# d102-spinsemi-fx.net
KiCad netlist of a schematic drawn in EAGLE
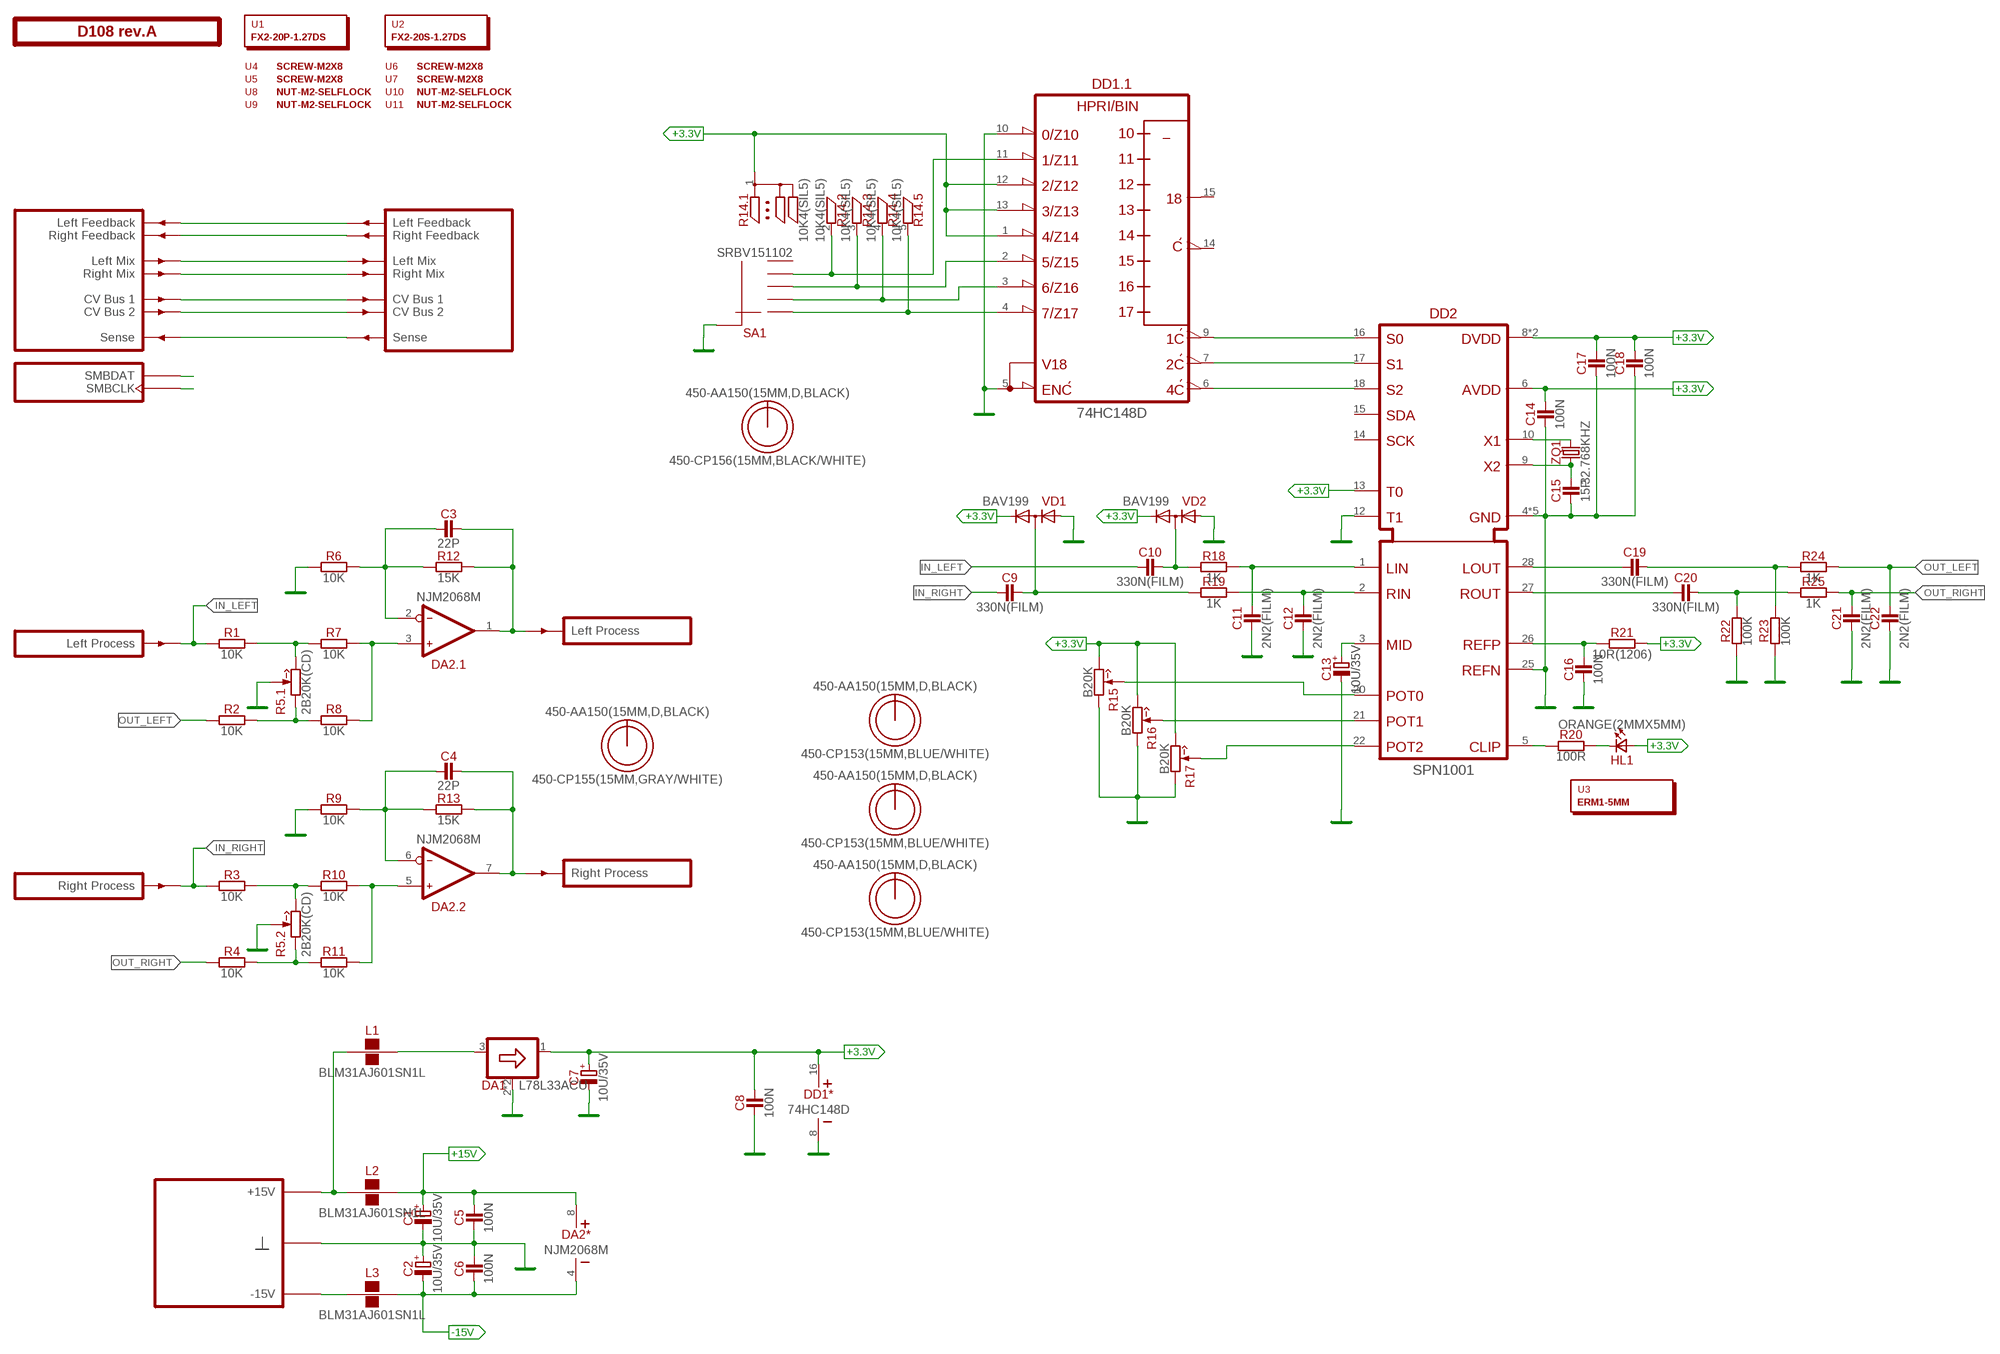
[diagram p0: schematic, sheet 1]

(export (version "E")
  (design (tool "Eeschema 10.0.6"))
  (components
    (comp (ref "C1")
      (value "10U/35V")
      (footprint "eagle-import:E2-5")
      (libsource (lib "eagle-import") (part "?10U/35V"))
    )
    (comp (ref "C2")
      (value "10U/35V")
      (footprint "eagle-import:E2-5")
      (libsource (lib "eagle-import") (part "?10U/35V"))
    )
    (comp (ref "C3")
      (value "22P")
      (footprint "eagle-import:C-0805")
      (libsource (lib "eagle-import") (part "?22P"))
    )
    (comp (ref "C4")
      (value "22P")
      (footprint "eagle-import:C-0805")
      (libsource (lib "eagle-import") (part "?22P"))
    )
    (comp (ref "C5")
      (value "100N")
      (footprint "eagle-import:C-0805")
      (libsource (lib "eagle-import") (part "?100N"))
    )
    (comp (ref "C6")
      (value "100N")
      (footprint "eagle-import:C-0805")
      (libsource (lib "eagle-import") (part "?100N"))
    )
    (comp (ref "C7")
      (value "10U/35V")
      (footprint "eagle-import:E2-5")
      (libsource (lib "eagle-import") (part "?10U/35V"))
    )
    (comp (ref "C8")
      (value "100N")
      (footprint "eagle-import:C-0805")
      (libsource (lib "eagle-import") (part "?100N"))
    )
    (comp (ref "C9")
      (value "330N(FILM)")
      (footprint "eagle-import:C050-035X075")
      (libsource (lib "eagle-import") (part "?330N(FILM)"))
    )
    (comp (ref "C10")
      (value "330N(FILM)")
      (footprint "eagle-import:C050-035X075")
      (libsource (lib "eagle-import") (part "?330N(FILM)"))
    )
    (comp (ref "C11")
      (value "2N2(FILM)")
      (footprint "eagle-import:C050-025X075")
      (libsource (lib "eagle-import") (part "?2N2(FILM)"))
    )
    (comp (ref "C12")
      (value "2N2(FILM)")
      (footprint "eagle-import:C050-025X075")
      (libsource (lib "eagle-import") (part "?2N2(FILM)"))
    )
    (comp (ref "C13")
      (value "10U/35V")
      (footprint "eagle-import:E2-5")
      (libsource (lib "eagle-import") (part "?10U/35V"))
    )
    (comp (ref "C14")
      (value "100N")
      (footprint "eagle-import:C-0805")
      (libsource (lib "eagle-import") (part "?100N"))
    )
    (comp (ref "C15")
      (value "15P")
      (footprint "eagle-import:C-0805")
      (libsource (lib "eagle-import") (part "?15P"))
    )
    (comp (ref "C16")
      (value "100N")
      (footprint "eagle-import:C-0805")
      (libsource (lib "eagle-import") (part "?100N"))
    )
    (comp (ref "C17")
      (value "100N")
      (footprint "eagle-import:C-0805")
      (libsource (lib "eagle-import") (part "?100N"))
    )
    (comp (ref "C18")
      (value "100N")
      (footprint "eagle-import:C-0805")
      (libsource (lib "eagle-import") (part "?100N"))
    )
    (comp (ref "C19")
      (value "330N(FILM)")
      (footprint "eagle-import:C050-035X075")
      (libsource (lib "eagle-import") (part "?330N(FILM)"))
    )
    (comp (ref "C20")
      (value "330N(FILM)")
      (footprint "eagle-import:C050-035X075")
      (libsource (lib "eagle-import") (part "?330N(FILM)"))
    )
    (comp (ref "C21")
      (value "2N2(FILM)")
      (footprint "eagle-import:C050-025X075")
      (libsource (lib "eagle-import") (part "?2N2(FILM)"))
    )
    (comp (ref "C22")
      (value "2N2(FILM)")
      (footprint "eagle-import:C050-025X075")
      (libsource (lib "eagle-import") (part "?2N2(FILM)"))
    )
    (comp (ref "DA1")
      (value "L78L33ACU")
      (footprint "eagle-import:SOT89")
      (libsource (lib "eagle-import") (part "?L78L33ACU"))
    )
    (comp (ref "DA2")
      (value "NJM2068M")
      (footprint "eagle-import:SO-8")
      (libsource (lib "eagle-import") (part "NJM2068M"))
    )
    (comp (ref "DD1")
      (value "74HC148D")
      (footprint "eagle-import:SO-16")
      (libsource (lib "eagle-import") (part "74148?DHC"))
    )
    (comp (ref "DD2")
      (value "SPN1001")
      (footprint "eagle-import:SO28W")
      (libsource (lib "eagle-import") (part "SPN1001"))
    )
    (comp (ref "HL1")
      (value "ORANGE(2MMX5MM)")
      (footprint "eagle-import:LED2X5")
      (libsource (lib "eagle-import") (part "?(2MMX5MM)ORANGE"))
    )
    (comp (ref "L1")
      (value "BLM31AJ601SN1L")
      (footprint "eagle-import:1206")
      (libsource (lib "eagle-import") (part "BLM31AJ601SN1L"))
    )
    (comp (ref "L2")
      (value "BLM31AJ601SN1L")
      (footprint "eagle-import:1206")
      (libsource (lib "eagle-import") (part "BLM31AJ601SN1L"))
    )
    (comp (ref "L3")
      (value "BLM31AJ601SN1L")
      (footprint "eagle-import:1206")
      (libsource (lib "eagle-import") (part "BLM31AJ601SN1L"))
    )
    (comp (ref "O2")
      (value "450-AA150(15MM,D,BLACK)")
      (footprint "eagle-import:EMPTY")
      (libsource (lib "eagle-import") (part "450-AA?150(15MM,D,BLACK)"))
    )
    (comp (ref "O3")
      (value "450-CP155(15MM,GRAY/WHITE)")
      (footprint "eagle-import:EMPTY")
      (libsource (lib "eagle-import") (part "450-C?P155(15MM,GRAY/WHITE)"))
    )
    (comp (ref "O4")
      (value "450-AA150(15MM,D,BLACK)")
      (footprint "eagle-import:EMPTY")
      (libsource (lib "eagle-import") (part "450-AA?150(15MM,D,BLACK)"))
    )
    (comp (ref "O5")
      (value "450-CP156(15MM,BLACK/WHITE)")
      (footprint "eagle-import:EMPTY")
      (libsource (lib "eagle-import") (part "450-C?P156(15MM,BLACK/WHITE)"))
    )
    (comp (ref "O6")
      (value "450-AA150(15MM,D,BLACK)")
      (footprint "eagle-import:EMPTY")
      (libsource (lib "eagle-import") (part "450-AA?150(15MM,D,BLACK)"))
    )
    (comp (ref "O7")
      (value "450-CP153(15MM,BLUE/WHITE)")
      (footprint "eagle-import:EMPTY")
      (libsource (lib "eagle-import") (part "450-C?P153(15MM,BLUE/WHITE)"))
    )
    (comp (ref "O8")
      (value "450-AA150(15MM,D,BLACK)")
      (footprint "eagle-import:EMPTY")
      (libsource (lib "eagle-import") (part "450-AA?150(15MM,D,BLACK)"))
    )
    (comp (ref "O9")
      (value "450-CP153(15MM,BLUE/WHITE)")
      (footprint "eagle-import:EMPTY")
      (libsource (lib "eagle-import") (part "450-C?P153(15MM,BLUE/WHITE)"))
    )
    (comp (ref "O10")
      (value "450-AA150(15MM,D,BLACK)")
      (footprint "eagle-import:EMPTY")
      (libsource (lib "eagle-import") (part "450-AA?150(15MM,D,BLACK)"))
    )
    (comp (ref "O11")
      (value "450-CP153(15MM,BLUE/WHITE)")
      (footprint "eagle-import:EMPTY")
      (libsource (lib "eagle-import") (part "450-C?P153(15MM,BLUE/WHITE)"))
    )
    (comp (ref "PCB1")
      (value "D108 rev.A")
      (footprint "eagle-import:ST2-BOARD-50")
      (libsource (lib "eagle-import") (part "ST2-BOARD-?50"))
    )
    (comp (ref "R1")
      (value "10K")
      (footprint "eagle-import:R-0805")
      (libsource (lib "eagle-import") (part "?10K"))
    )
    (comp (ref "R2")
      (value "10K")
      (footprint "eagle-import:R-0805")
      (libsource (lib "eagle-import") (part "?10K"))
    )
    (comp (ref "R3")
      (value "10K")
      (footprint "eagle-import:R-0805")
      (libsource (lib "eagle-import") (part "?10K"))
    )
    (comp (ref "R4")
      (value "10K")
      (footprint "eagle-import:R-0805")
      (libsource (lib "eagle-import") (part "?10K"))
    )
    (comp (ref "R5")
      (value "2B20K(CD)")
      (footprint "eagle-import:RV11-DUAL")
      (libsource (lib "eagle-import") (part "2?B20K(CD)"))
    )
    (comp (ref "R6")
      (value "10K")
      (footprint "eagle-import:R-0805")
      (libsource (lib "eagle-import") (part "?10K"))
    )
    (comp (ref "R7")
      (value "10K")
      (footprint "eagle-import:R-0805")
      (libsource (lib "eagle-import") (part "?10K"))
    )
    (comp (ref "R8")
      (value "10K")
      (footprint "eagle-import:R-0805")
      (libsource (lib "eagle-import") (part "?10K"))
    )
    (comp (ref "R9")
      (value "10K")
      (footprint "eagle-import:R-0805")
      (libsource (lib "eagle-import") (part "?10K"))
    )
    (comp (ref "R10")
      (value "10K")
      (footprint "eagle-import:R-0805")
      (libsource (lib "eagle-import") (part "?10K"))
    )
    (comp (ref "R11")
      (value "10K")
      (footprint "eagle-import:R-0805")
      (libsource (lib "eagle-import") (part "?10K"))
    )
    (comp (ref "R12")
      (value "15K")
      (footprint "eagle-import:R-0805")
      (libsource (lib "eagle-import") (part "?15K"))
    )
    (comp (ref "R13")
      (value "15K")
      (footprint "eagle-import:R-0805")
      (libsource (lib "eagle-import") (part "?15K"))
    )
    (comp (ref "R14")
      (value "10K4(SIL5)")
      (footprint "eagle-import:R-SIL5")
      (libsource (lib "eagle-import") (part "?4(SIL5)10K"))
    )
    (comp (ref "R15")
      (value "B20K")
      (footprint "eagle-import:RV11-SINGLE")
      (libsource (lib "eagle-import") (part "?B20K"))
    )
    (comp (ref "R16")
      (value "B20K")
      (footprint "eagle-import:RV11-SINGLE")
      (libsource (lib "eagle-import") (part "?B20K"))
    )
    (comp (ref "R17")
      (value "B20K")
      (footprint "eagle-import:RV11-SINGLE")
      (libsource (lib "eagle-import") (part "?B20K"))
    )
    (comp (ref "R18")
      (value "1K")
      (footprint "eagle-import:R-0805")
      (libsource (lib "eagle-import") (part "?1K"))
    )
    (comp (ref "R19")
      (value "1K")
      (footprint "eagle-import:R-0805")
      (libsource (lib "eagle-import") (part "?1K"))
    )
    (comp (ref "R20")
      (value "100R")
      (footprint "eagle-import:R-0805")
      (libsource (lib "eagle-import") (part "?100R"))
    )
    (comp (ref "R21")
      (value "10R(1206)")
      (footprint "eagle-import:R-1206")
      (libsource (lib "eagle-import") (part "?10R(1206)"))
    )
    (comp (ref "R22")
      (value "100K")
      (footprint "eagle-import:R-0805")
      (libsource (lib "eagle-import") (part "?100K"))
    )
    (comp (ref "R23")
      (value "100K")
      (footprint "eagle-import:R-0805")
      (libsource (lib "eagle-import") (part "?100K"))
    )
    (comp (ref "R24")
      (value "1K")
      (footprint "eagle-import:R-0805")
      (libsource (lib "eagle-import") (part "?1K"))
    )
    (comp (ref "R25")
      (value "1K")
      (footprint "eagle-import:R-0805")
      (libsource (lib "eagle-import") (part "?1K"))
    )
    (comp (ref "SA1")
      (value "SRBV151102")
      (footprint "eagle-import:SRBV")
      (libsource (lib "eagle-import") (part "SRBV151102"))
    )
    (comp (ref "U1")
      (value "FX2-20P-1.27DS")
      (footprint "eagle-import:EMPTY")
      (libsource (lib "eagle-import") (part "?FX2-20P-1.27DS"))
    )
    (comp (ref "U2")
      (value "FX2-20S-1.27DS")
      (footprint "eagle-import:EMPTY")
      (libsource (lib "eagle-import") (part "?FX2-20S-1.27DS"))
    )
    (comp (ref "U3")
      (value "ERM1-5MM")
      (footprint "eagle-import:EMPTY")
      (libsource (lib "eagle-import") (part "?ERM1-5MM"))
    )
    (comp (ref "U4")
      (value "SCREW-M2X8")
      (footprint "eagle-import:EMPTY")
      (libsource (lib "eagle-import") (part "?SCREW-M2X8"))
    )
    (comp (ref "U5")
      (value "SCREW-M2X8")
      (footprint "eagle-import:EMPTY")
      (libsource (lib "eagle-import") (part "?SCREW-M2X8"))
    )
    (comp (ref "U6")
      (value "SCREW-M2X8")
      (footprint "eagle-import:EMPTY")
      (libsource (lib "eagle-import") (part "?SCREW-M2X8"))
    )
    (comp (ref "U7")
      (value "SCREW-M2X8")
      (footprint "eagle-import:EMPTY")
      (libsource (lib "eagle-import") (part "?SCREW-M2X8"))
    )
    (comp (ref "U8")
      (value "NUT-M2-SELFLOCK")
      (footprint "eagle-import:EMPTY")
      (libsource (lib "eagle-import") (part "?NUT-M2-SELFLOCK"))
    )
    (comp (ref "U9")
      (value "NUT-M2-SELFLOCK")
      (footprint "eagle-import:EMPTY")
      (libsource (lib "eagle-import") (part "?NUT-M2-SELFLOCK"))
    )
    (comp (ref "U10")
      (value "NUT-M2-SELFLOCK")
      (footprint "eagle-import:EMPTY")
      (libsource (lib "eagle-import") (part "?NUT-M2-SELFLOCK"))
    )
    (comp (ref "U11")
      (value "NUT-M2-SELFLOCK")
      (footprint "eagle-import:EMPTY")
      (libsource (lib "eagle-import") (part "?NUT-M2-SELFLOCK"))
    )
    (comp (ref "VD1")
      (value "BAV199")
      (footprint "eagle-import:SOT23")
      (libsource (lib "eagle-import") (part "BAV199"))
    )
    (comp (ref "VD2")
      (value "BAV199")
      (footprint "eagle-import:SOT23")
      (libsource (lib "eagle-import") (part "BAV199"))
    )
    (comp (ref "ZQ1")
      (value "32.768KHZ")
      (footprint "eagle-import:3215")
      (libsource (lib "eagle-import") (part "?32.768KHZ"))
    )
  )
  (nets
    (net (code "1") (name "+3.3V") (class "Default")
      (node (ref "C14") (pin "2") (pinfunction "2_2") (pintype "passive"))
      (node (ref "C17") (pin "2") (pinfunction "2_2") (pintype "passive"))
      (node (ref "C18") (pin "2") (pinfunction "2_2") (pintype "passive"))
      (node (ref "C7") (pin "+") (pinfunction "+_+") (pintype "passive"))
      (node (ref "C8") (pin "2") (pinfunction "2_2") (pintype "passive"))
      (node (ref "DA1") (pin "1") (pinfunction "OUT_1") (pintype "power_in"))
      (node (ref "DD1") (pin "1") (pinfunction "4_1") (pintype "input"))
      (node (ref "DD1") (pin "12") (pinfunction "2_12") (pintype "input"))
      (node (ref "DD1") (pin "13") (pinfunction "3_13") (pintype "input"))
      (node (ref "DD1") (pin "16") (pinfunction "V+_16") (pintype "power_in"))
      (node (ref "DD2") (pin "13") (pinfunction "T0_13") (pintype "input"))
      (node (ref "DD2") (pin "23") (pinfunction "DVDD_23") (pintype "input"))
      (node (ref "DD2") (pin "6") (pinfunction "AVDD_6") (pintype "input"))
      (node (ref "DD2") (pin "8") (pinfunction "DVDD_8") (pintype "input"))
      (node (ref "HL1") (pin "A") (pinfunction "A_A") (pintype "passive"))
      (node (ref "R14") (pin "1") (pinfunction "R_1") (pintype "passive"))
      (node (ref "R15") (pin "3") (pinfunction "CW_3") (pintype "passive"))
      (node (ref "R16") (pin "3") (pinfunction "CW_3") (pintype "passive"))
      (node (ref "R17") (pin "3") (pinfunction "CW_3") (pintype "passive"))
      (node (ref "R21") (pin "2") (pinfunction "2_2") (pintype "passive"))
      (node (ref "VD1") (pin "2") (pinfunction "C_2") (pintype "passive"))
      (node (ref "VD2") (pin "2") (pinfunction "C_2") (pintype "passive"))
    )
    (net (code "2") (name "+15V") (class "Default")
      (node (ref "C1") (pin "+") (pinfunction "+_+") (pintype "passive"))
      (node (ref "C5") (pin "2") (pinfunction "2_2") (pintype "passive"))
      (node (ref "DA2") (pin "8") (pinfunction "V+_8") (pintype "power_in"))
      (node (ref "L2") (pin "2") (pinfunction "2_2") (pintype "passive"))
    )
    (net (code "3") (name "-15V") (class "Default")
      (node (ref "C2") (pin "-") (pinfunction "-_-") (pintype "passive"))
      (node (ref "C6") (pin "1") (pinfunction "1_1") (pintype "passive"))
      (node (ref "DA2") (pin "4") (pinfunction "V-_4") (pintype "power_in"))
      (node (ref "L3") (pin "2") (pinfunction "2_2") (pintype "passive"))
    )
    (net (code "4") (name "GND") (class "Default")
      (node (ref "C1") (pin "-") (pinfunction "-_-") (pintype "passive"))
      (node (ref "C11") (pin "1") (pinfunction "1_1") (pintype "passive"))
      (node (ref "C12") (pin "1") (pinfunction "1_1") (pintype "passive"))
      (node (ref "C13") (pin "-") (pinfunction "-_-") (pintype "passive"))
      (node (ref "C14") (pin "1") (pinfunction "1_1") (pintype "passive"))
      (node (ref "C15") (pin "1") (pinfunction "1_1") (pintype "passive"))
      (node (ref "C16") (pin "1") (pinfunction "1_1") (pintype "passive"))
      (node (ref "C17") (pin "1") (pinfunction "1_1") (pintype "passive"))
      (node (ref "C18") (pin "1") (pinfunction "1_1") (pintype "passive"))
      (node (ref "C2") (pin "+") (pinfunction "+_+") (pintype "passive"))
      (node (ref "C21") (pin "1") (pinfunction "1_1") (pintype "passive"))
      (node (ref "C22") (pin "1") (pinfunction "1_1") (pintype "passive"))
      (node (ref "C5") (pin "1") (pinfunction "1_1") (pintype "passive"))
      (node (ref "C6") (pin "2") (pinfunction "2_2") (pintype "passive"))
      (node (ref "C7") (pin "-") (pinfunction "-_-") (pintype "passive"))
      (node (ref "C8") (pin "1") (pinfunction "1_1") (pintype "passive"))
      (node (ref "DA1") (pin "2") (pinfunction "GND_2") (pintype "power_in"))
      (node (ref "DA1") (pin "2@1") (pinfunction "GND_2@1") (pintype "power_in"))
      (node (ref "DD1") (pin "10") (pinfunction "0_10") (pintype "input"))
      (node (ref "DD1") (pin "5") (pinfunction "EI_5") (pintype "input"))
      (node (ref "DD1") (pin "8") (pinfunction "V-_8") (pintype "power_in"))
      (node (ref "DD2") (pin "11") (pinfunction "GND_11") (pintype "input"))
      (node (ref "DD2") (pin "12") (pinfunction "T1_12") (pintype "input"))
      (node (ref "DD2") (pin "19") (pinfunction "GND_19") (pintype "input"))
      (node (ref "DD2") (pin "24") (pinfunction "GND_24") (pintype "input"))
      (node (ref "DD2") (pin "25") (pinfunction "REFN_25") (pintype "input"))
      (node (ref "DD2") (pin "4") (pinfunction "GND_4") (pintype "input"))
      (node (ref "DD2") (pin "7") (pinfunction "GND_7") (pintype "input"))
      (node (ref "PCB1") (pin "B4") (pinfunction "GND_B4") (pintype "bidirectional"))
      (node (ref "PCB1") (pin "B4'") (pinfunction "GND_B4'") (pintype "bidirectional"))
      (node (ref "PCB1") (pin "B5") (pinfunction "GND_B5") (pintype "bidirectional"))
      (node (ref "PCB1") (pin "B5'") (pinfunction "GND_B5'") (pintype "bidirectional"))
      (node (ref "PCB1") (pin "B6") (pinfunction "GND_B6") (pintype "bidirectional"))
      (node (ref "PCB1") (pin "B6'") (pinfunction "GND_B6'") (pintype "bidirectional"))
      (node (ref "PCB1") (pin "B7") (pinfunction "GND_B7") (pintype "bidirectional"))
      (node (ref "PCB1") (pin "B7'") (pinfunction "GND_B7'") (pintype "bidirectional"))
      (node (ref "PCB1") (pin "B8") (pinfunction "GND_B8") (pintype "bidirectional"))
      (node (ref "PCB1") (pin "B8'") (pinfunction "GND_B8'") (pintype "bidirectional"))
      (node (ref "R15") (pin "1") (pinfunction "CCW_1") (pintype "passive"))
      (node (ref "R16") (pin "1") (pinfunction "CCW_1") (pintype "passive"))
      (node (ref "R17") (pin "1") (pinfunction "CCW_1") (pintype "passive"))
      (node (ref "R22") (pin "1") (pinfunction "1_1") (pintype "passive"))
      (node (ref "R23") (pin "1") (pinfunction "1_1") (pintype "passive"))
      (node (ref "R5") (pin "2") (pinfunction "W_2") (pintype "passive"))
      (node (ref "R5") (pin "2'") (pinfunction "W_2'") (pintype "passive"))
      (node (ref "R6") (pin "1") (pinfunction "1_1") (pintype "passive"))
      (node (ref "R9") (pin "1") (pinfunction "1_1") (pintype "passive"))
      (node (ref "SA1") (pin "1") (pinfunction "CM_1") (pintype "passive"))
      (node (ref "SA1") (pin "10") (pinfunction "CM_10") (pintype "passive"))
      (node (ref "VD1") (pin "1") (pinfunction "A_1") (pintype "passive"))
      (node (ref "VD2") (pin "1") (pinfunction "A_1") (pintype "passive"))
    )
    (net (code "5") (name "IN_LEFT") (class "Default")
      (node (ref "C10") (pin "1") (pinfunction "1_1") (pintype "passive"))
      (node (ref "PCB1") (pin "BINL") (pinfunction "INL_BINL") (pintype "bidirectional"))
      (node (ref "R1") (pin "1") (pinfunction "1_1") (pintype "passive"))
    )
    (net (code "6") (name "IN_RIGHT") (class "Default")
      (node (ref "C9") (pin "1") (pinfunction "1_1") (pintype "passive"))
      (node (ref "PCB1") (pin "BINR") (pinfunction "INR_BINR") (pintype "bidirectional"))
      (node (ref "R3") (pin "1") (pinfunction "1_1") (pintype "passive"))
    )
    (net (code "7") (name "Net-(C19-Pad2)") (class "Default")
      (node (ref "C19") (pin "2") (pinfunction "2_2") (pintype "passive"))
      (node (ref "R23") (pin "2") (pinfunction "2_2") (pintype "passive"))
      (node (ref "R24") (pin "1") (pinfunction "1_1") (pintype "passive"))
    )
    (net (code "8") (name "Net-(C20-Pad2)") (class "Default")
      (node (ref "C20") (pin "2") (pinfunction "2_2") (pintype "passive"))
      (node (ref "R22") (pin "2") (pinfunction "2_2") (pintype "passive"))
      (node (ref "R25") (pin "1") (pinfunction "1_1") (pintype "passive"))
    )
    (net (code "9") (name "Net-(DA1-IN)") (class "Default")
      (node (ref "DA1") (pin "3") (pinfunction "IN_3") (pintype "power_in"))
      (node (ref "L1") (pin "2") (pinfunction "2_2") (pintype "passive"))
    )
    (net (code "10") (name "Net-(DA2B-IN+)") (class "Default")
      (node (ref "DA2") (pin "3") (pinfunction "IN+_3") (pintype "input"))
      (node (ref "R7") (pin "2") (pinfunction "2_2") (pintype "passive"))
      (node (ref "R8") (pin "2") (pinfunction "2_2") (pintype "passive"))
    )
    (net (code "11") (name "Net-(DA2B-IN-)") (class "Default")
      (node (ref "C3") (pin "1") (pinfunction "1_1") (pintype "passive"))
      (node (ref "DA2") (pin "2") (pinfunction "IN-_2") (pintype "input"))
      (node (ref "R12") (pin "1") (pinfunction "1_1") (pintype "passive"))
      (node (ref "R6") (pin "2") (pinfunction "2_2") (pintype "passive"))
    )
    (net (code "12") (name "Net-(DA2B-OUT)") (class "Default")
      (node (ref "C3") (pin "2") (pinfunction "2_2") (pintype "passive"))
      (node (ref "DA2") (pin "1") (pinfunction "OUT_1") (pintype "output"))
      (node (ref "PCB1") (pin "BOUTL'") (pinfunction "OUTL_BOUTL'") (pintype "bidirectional"))
      (node (ref "R12") (pin "2") (pinfunction "2_2") (pintype "passive"))
    )
    (net (code "13") (name "Net-(DA2C-IN+)") (class "Default")
      (node (ref "DA2") (pin "5") (pinfunction "IN+_5") (pintype "input"))
      (node (ref "R10") (pin "2") (pinfunction "2_2") (pintype "passive"))
      (node (ref "R11") (pin "2") (pinfunction "2_2") (pintype "passive"))
    )
    (net (code "14") (name "Net-(DA2C-IN-)") (class "Default")
      (node (ref "C4") (pin "1") (pinfunction "1_1") (pintype "passive"))
      (node (ref "DA2") (pin "6") (pinfunction "IN-_6") (pintype "input"))
      (node (ref "R13") (pin "1") (pinfunction "1_1") (pintype "passive"))
      (node (ref "R9") (pin "2") (pinfunction "2_2") (pintype "passive"))
    )
    (net (code "15") (name "Net-(DA2C-OUT)") (class "Default")
      (node (ref "C4") (pin "2") (pinfunction "2_2") (pintype "passive"))
      (node (ref "DA2") (pin "7") (pinfunction "OUT_7") (pintype "output"))
      (node (ref "PCB1") (pin "BOUTR'") (pinfunction "OUTR_BOUTR'") (pintype "bidirectional"))
      (node (ref "R13") (pin "2") (pinfunction "2_2") (pintype "passive"))
    )
    (net (code "16") (name "Net-(DD1B-1)") (class "Default")
      (node (ref "DD1") (pin "11") (pinfunction "1_11") (pintype "input"))
      (node (ref "R14") (pin "2") (pinfunction "R_2") (pintype "passive"))
      (node (ref "SA1") (pin "5") (pinfunction "4_5") (pintype "passive"))
    )
    (net (code "17") (name "Net-(DD1B-5)") (class "Default")
      (node (ref "DD1") (pin "2") (pinfunction "5_2") (pintype "input"))
      (node (ref "R14") (pin "3") (pinfunction "R_3") (pintype "passive"))
      (node (ref "SA1") (pin "4") (pinfunction "3_4") (pintype "passive"))
    )
    (net (code "18") (name "Net-(DD1B-6)") (class "Default")
      (node (ref "DD1") (pin "3") (pinfunction "6_3") (pintype "input"))
      (node (ref "R14") (pin "4") (pinfunction "R_4") (pintype "passive"))
      (node (ref "SA1") (pin "3") (pinfunction "2_3") (pintype "passive"))
    )
    (net (code "19") (name "Net-(DD1B-7)") (class "Default")
      (node (ref "DD1") (pin "4") (pinfunction "7_4") (pintype "input"))
      (node (ref "R14") (pin "5") (pinfunction "R_5") (pintype "passive"))
      (node (ref "SA1") (pin "2") (pinfunction "1_2") (pintype "passive"))
    )
    (net (code "20") (name "Net-(DD1B-A0)") (class "Default")
      (node (ref "DD1") (pin "9") (pinfunction "A0_9") (pintype "output"))
      (node (ref "DD2") (pin "16") (pinfunction "S0_16") (pintype "input"))
    )
    (net (code "21") (name "Net-(DD1B-A1)") (class "Default")
      (node (ref "DD1") (pin "7") (pinfunction "A1_7") (pintype "output"))
      (node (ref "DD2") (pin "17") (pinfunction "S1_17") (pintype "input"))
    )
    (net (code "22") (name "Net-(DD1B-A2)") (class "Default")
      (node (ref "DD1") (pin "6") (pinfunction "A2_6") (pintype "output"))
      (node (ref "DD2") (pin "18") (pinfunction "S2_18") (pintype "input"))
    )
    (net (code "23") (name "Net-(DD2-CLIP)") (class "Default")
      (node (ref "DD2") (pin "5") (pinfunction "CLIP_5") (pintype "input"))
      (node (ref "R20") (pin "1") (pinfunction "1_1") (pintype "passive"))
    )
    (net (code "24") (name "Net-(DD2-LIN)") (class "Default")
      (node (ref "C11") (pin "2") (pinfunction "2_2") (pintype "passive"))
      (node (ref "DD2") (pin "1") (pinfunction "LIN_1") (pintype "input"))
      (node (ref "R18") (pin "2") (pinfunction "2_2") (pintype "passive"))
    )
    (net (code "25") (name "Net-(DD2-LOUT)") (class "Default")
      (node (ref "C19") (pin "1") (pinfunction "1_1") (pintype "passive"))
      (node (ref "DD2") (pin "28") (pinfunction "LOUT_28") (pintype "input"))
    )
    (net (code "26") (name "Net-(DD2-MID)") (class "Default")
      (node (ref "C13") (pin "+") (pinfunction "+_+") (pintype "passive"))
      (node (ref "DD2") (pin "3") (pinfunction "MID_3") (pintype "input"))
    )
    (net (code "27") (name "Net-(DD2-POT0)") (class "Default")
      (node (ref "DD2") (pin "20") (pinfunction "POT0_20") (pintype "input"))
      (node (ref "R15") (pin "2") (pinfunction "W_2") (pintype "passive"))
    )
    (net (code "28") (name "Net-(DD2-POT1)") (class "Default")
      (node (ref "DD2") (pin "21") (pinfunction "POT1_21") (pintype "input"))
      (node (ref "R16") (pin "2") (pinfunction "W_2") (pintype "passive"))
    )
    (net (code "29") (name "Net-(DD2-POT2)") (class "Default")
      (node (ref "DD2") (pin "22") (pinfunction "POT2_22") (pintype "input"))
      (node (ref "R17") (pin "2") (pinfunction "W_2") (pintype "passive"))
    )
    (net (code "30") (name "Net-(DD2-REFP)") (class "Default")
      (node (ref "C16") (pin "2") (pinfunction "2_2") (pintype "passive"))
      (node (ref "DD2") (pin "26") (pinfunction "REFP_26") (pintype "input"))
      (node (ref "R21") (pin "1") (pinfunction "1_1") (pintype "passive"))
    )
    (net (code "31") (name "Net-(DD2-RIN)") (class "Default")
      (node (ref "C12") (pin "2") (pinfunction "2_2") (pintype "passive"))
      (node (ref "DD2") (pin "2") (pinfunction "RIN_2") (pintype "input"))
      (node (ref "R19") (pin "2") (pinfunction "2_2") (pintype "passive"))
    )
    (net (code "32") (name "Net-(DD2-ROUT)") (class "Default")
      (node (ref "C20") (pin "1") (pinfunction "1_1") (pintype "passive"))
      (node (ref "DD2") (pin "27") (pinfunction "ROUT_27") (pintype "input"))
    )
    (net (code "33") (name "Net-(DD2-X1)") (class "Default")
      (node (ref "DD2") (pin "10") (pinfunction "X1_10") (pintype "input"))
      (node (ref "ZQ1") (pin "2") (pinfunction "2_2") (pintype "passive"))
    )
    (net (code "34") (name "Net-(DD2-X2)") (class "Default")
      (node (ref "C15") (pin "2") (pinfunction "2_2") (pintype "passive"))
      (node (ref "DD2") (pin "9") (pinfunction "X2_9") (pintype "input"))
      (node (ref "ZQ1") (pin "1") (pinfunction "1_1") (pintype "passive"))
    )
    (net (code "35") (name "Net-(HL1-C)") (class "Default")
      (node (ref "HL1") (pin "K") (pinfunction "C_K") (pintype "passive"))
      (node (ref "R20") (pin "2") (pinfunction "2_2") (pintype "passive"))
    )
    (net (code "36") (name "Net-(L1-Pad1)") (class "Default")
      (node (ref "L1") (pin "1") (pinfunction "1_1") (pintype "passive"))
      (node (ref "L2") (pin "1") (pinfunction "1_1") (pintype "passive"))
      (node (ref "PCB1") (pin "A+15") (pinfunction "P+15V_A+15") (pintype "bidirectional"))
      (node (ref "PCB1") (pin "A+15'") (pinfunction "P+15V_A+15'") (pintype "bidirectional"))
      (node (ref "PCB1") (pin "B+15") (pinfunction "P+15V_B+15") (pintype "bidirectional"))
      (node (ref "PCB1") (pin "B+15'") (pinfunction "P+15V_B+15'") (pintype "bidirectional"))
    )
    (net (code "37") (name "Net-(L3-Pad1)") (class "Default")
      (node (ref "L3") (pin "1") (pinfunction "1_1") (pintype "passive"))
      (node (ref "PCB1") (pin "A-15") (pinfunction "P-15V_A-15") (pintype "bidirectional"))
      (node (ref "PCB1") (pin "A-15'") (pinfunction "P-15V_A-15'") (pintype "bidirectional"))
      (node (ref "PCB1") (pin "B-15") (pinfunction "P-15V_B-15") (pintype "bidirectional"))
      (node (ref "PCB1") (pin "B-15'") (pinfunction "P-15V_B-15'") (pintype "bidirectional"))
    )
    (net (code "38") (name "Net-(PCB1F-CV1)") (class "Default")
      (node (ref "PCB1") (pin "ACV1") (pinfunction "CV1_ACV1") (pintype "bidirectional"))
      (node (ref "PCB1") (pin "ACV1'") (pinfunction "CV1'_ACV1'") (pintype "bidirectional"))
    )
    (net (code "39") (name "Net-(PCB1F-CV2)") (class "Default")
      (node (ref "PCB1") (pin "ACV2") (pinfunction "CV2_ACV2") (pintype "bidirectional"))
      (node (ref "PCB1") (pin "ACV2'") (pinfunction "CV2'_ACV2'") (pintype "bidirectional"))
    )
    (net (code "40") (name "Net-(PCB1F-LFBK)") (class "Default")
      (node (ref "PCB1") (pin "ALFBK") (pinfunction "LFBK_ALFBK") (pintype "bidirectional"))
      (node (ref "PCB1") (pin "ALFBK'") (pinfunction "LFBK'_ALFBK'") (pintype "bidirectional"))
    )
    (net (code "41") (name "Net-(PCB1F-LMIX)") (class "Default")
      (node (ref "PCB1") (pin "ALMIX") (pinfunction "LMIX_ALMIX") (pintype "bidirectional"))
      (node (ref "PCB1") (pin "ALMIX'") (pinfunction "LMIX'_ALMIX'") (pintype "bidirectional"))
    )
    (net (code "42") (name "Net-(PCB1F-RFBK)") (class "Default")
      (node (ref "PCB1") (pin "ARFBK") (pinfunction "RFBK_ARFBK") (pintype "bidirectional"))
      (node (ref "PCB1") (pin "ARFBK'") (pinfunction "RFBK'_ARFBK'") (pintype "bidirectional"))
    )
    (net (code "43") (name "Net-(PCB1F-RMIX)") (class "Default")
      (node (ref "PCB1") (pin "ARMIX") (pinfunction "RMIX_ARMIX") (pintype "bidirectional"))
      (node (ref "PCB1") (pin "ARMIX'") (pinfunction "RMIX'_ARMIX'") (pintype "bidirectional"))
    )
    (net (code "44") (name "Net-(PCB1F-SENSE)") (class "Default")
      (node (ref "PCB1") (pin "BSENSE") (pinfunction "SENSE_BSENSE") (pintype "bidirectional"))
      (node (ref "PCB1") (pin "BSENSE'") (pinfunction "SENSE'_BSENSE'") (pintype "bidirectional"))
    )
    (net (code "45") (name "Net-(PCB1H-SMBCLK-PadASMBCLK')") (class "Default")
      (node (ref "PCB1") (pin "ASMBCLK") (pinfunction "SMBCLK_ASMBCLK") (pintype "bidirectional"))
      (node (ref "PCB1") (pin "ASMBCLK'") (pinfunction "SMBCLK_ASMBCLK'") (pintype "bidirectional"))
    )
    (net (code "46") (name "Net-(PCB1H-SMBDAT-PadASMBDAT')") (class "Default")
      (node (ref "PCB1") (pin "ASMBDAT") (pinfunction "SMBDAT_ASMBDAT") (pintype "bidirectional"))
      (node (ref "PCB1") (pin "ASMBDAT'") (pinfunction "SMBDAT_ASMBDAT'") (pintype "bidirectional"))
    )
    (net (code "47") (name "Net-(R5A-CCW)") (class "Default")
      (node (ref "R2") (pin "2") (pinfunction "2_2") (pintype "passive"))
      (node (ref "R5") (pin "1") (pinfunction "CCW_1") (pintype "passive"))
      (node (ref "R8") (pin "1") (pinfunction "1_1") (pintype "passive"))
    )
    (net (code "48") (name "Net-(R5A-CW)") (class "Default")
      (node (ref "R1") (pin "2") (pinfunction "2_2") (pintype "passive"))
      (node (ref "R5") (pin "3") (pinfunction "CW_3") (pintype "passive"))
      (node (ref "R7") (pin "1") (pinfunction "1_1") (pintype "passive"))
    )
    (net (code "49") (name "Net-(R5B-CCW)") (class "Default")
      (node (ref "R11") (pin "1") (pinfunction "1_1") (pintype "passive"))
      (node (ref "R4") (pin "2") (pinfunction "2_2") (pintype "passive"))
      (node (ref "R5") (pin "1'") (pinfunction "CCW_1'") (pintype "passive"))
    )
    (net (code "50") (name "Net-(R5B-CW)") (class "Default")
      (node (ref "R10") (pin "1") (pinfunction "1_1") (pintype "passive"))
      (node (ref "R3") (pin "2") (pinfunction "2_2") (pintype "passive"))
      (node (ref "R5") (pin "3'") (pinfunction "CW_3'") (pintype "passive"))
    )
    (net (code "51") (name "Net-(VD1-CMN)") (class "Default")
      (node (ref "C9") (pin "2") (pinfunction "2_2") (pintype "passive"))
      (node (ref "R19") (pin "1") (pinfunction "1_1") (pintype "passive"))
      (node (ref "VD1") (pin "3") (pinfunction "CMN_3") (pintype "passive"))
    )
    (net (code "52") (name "Net-(VD2-CMN)") (class "Default")
      (node (ref "C10") (pin "2") (pinfunction "2_2") (pintype "passive"))
      (node (ref "R18") (pin "1") (pinfunction "1_1") (pintype "passive"))
      (node (ref "VD2") (pin "3") (pinfunction "CMN_3") (pintype "passive"))
    )
    (net (code "53") (name "OUT_LEFT") (class "Default")
      (node (ref "C22") (pin "2") (pinfunction "2_2") (pintype "passive"))
      (node (ref "R2") (pin "1") (pinfunction "1_1") (pintype "passive"))
      (node (ref "R24") (pin "2") (pinfunction "2_2") (pintype "passive"))
    )
    (net (code "54") (name "OUT_RIGHT") (class "Default")
      (node (ref "C21") (pin "2") (pinfunction "2_2") (pintype "passive"))
      (node (ref "R25") (pin "2") (pinfunction "2_2") (pintype "passive"))
      (node (ref "R4") (pin "1") (pinfunction "1_1") (pintype "passive"))
    )
    (net (code "55") (name "unconnected-(DD1B-EO-Pad15)") (class "Default")
      (node (ref "DD1") (pin "15") (pinfunction "EO_15") (pintype "output"))
    )
    (net (code "56") (name "unconnected-(DD1B-GS-Pad14)") (class "Default")
      (node (ref "DD1") (pin "14") (pinfunction "GS_14") (pintype "output"))
    )
    (net (code "57") (name "unconnected-(DD2-SCK-Pad14)") (class "Default")
      (node (ref "DD2") (pin "14") (pinfunction "SCK_14") (pintype "input"))
    )
    (net (code "58") (name "unconnected-(DD2-SDA-Pad15)") (class "Default")
      (node (ref "DD2") (pin "15") (pinfunction "SDA_15") (pintype "input"))
    )
    (net (code "59") (name "unconnected-(SA1-5-Pad6)") (class "Default")
      (node (ref "SA1") (pin "6") (pinfunction "5_6") (pintype "passive"))
    )
  )
)
